# CH32L103K8U6-R0.net
KiCad netlist of a schematic drawn in Altium Designer
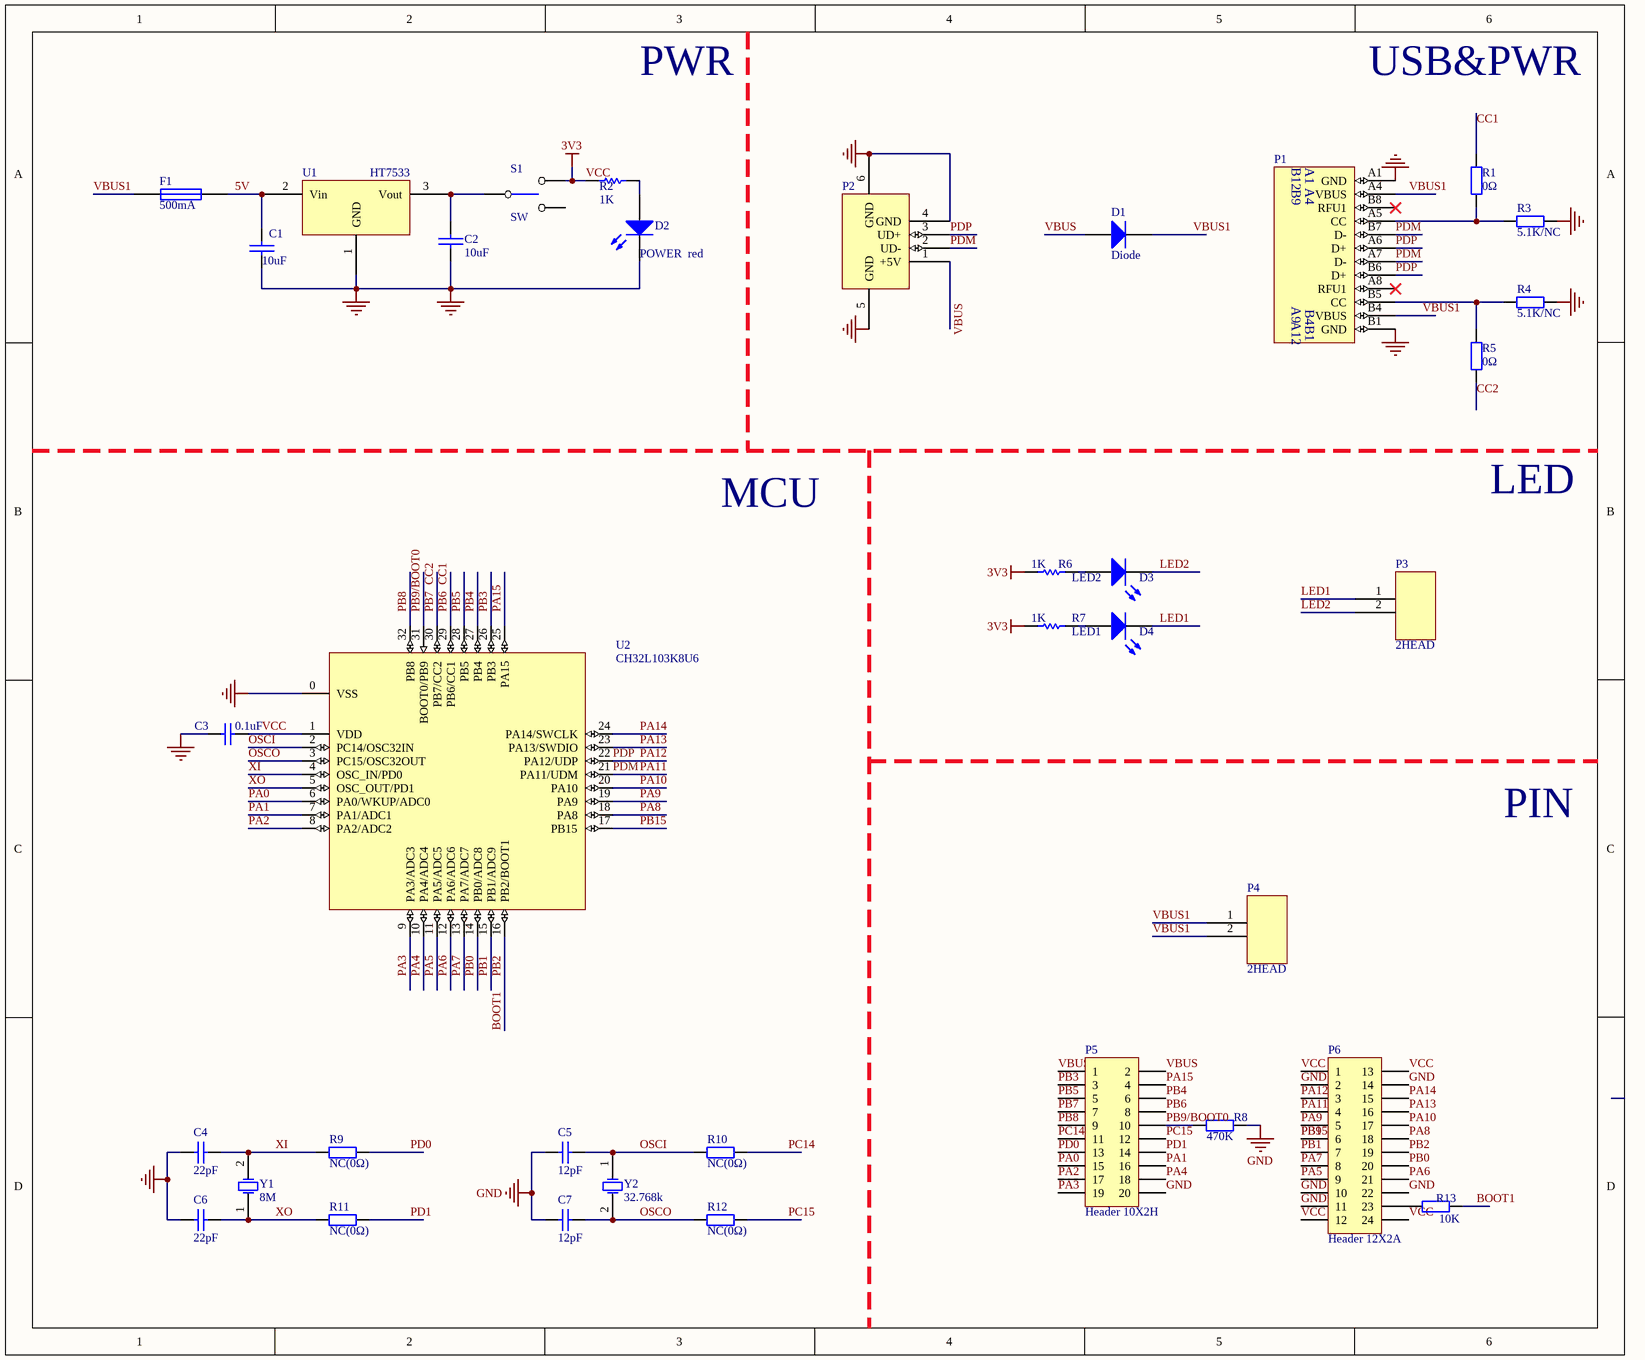
[diagram p0: CH32L103K8U6-R0.SchDoc]

(export (version "E")
  (design (tool "Eeschema 10.0.6"))
  (components
    (comp (ref "C1")
      (value "10uF")
      (footprint "0603_C")
      (description "Capacitor")
      (libsource (lib "*") (part "CAP"))
    )
    (comp (ref "C2")
      (value "10uF")
      (footprint "0603_C")
      (description "Capacitor")
      (libsource (lib "*") (part "CAP"))
    )
    (comp (ref "C3")
      (value "0.1uF")
      (footprint "0603_C")
      (description "Capacitor")
      (fields (field (name "PUBLISHER") "Altium Limited"))
      (libsource (lib "*") (part "Cap"))
    )
    (comp (ref "C4")
      (value "22pF")
      (footprint "0603_C")
      (description "Capacitor")
      (fields (field (name "PUBLISHER") "Altium Limited"))
      (libsource (lib "*") (part "Cap"))
    )
    (comp (ref "C5")
      (value "12pF")
      (footprint "0603")
      (description "Capacitor")
      (fields (field (name "PUBLISHER") "Altium Limited"))
      (libsource (lib "Miscellaneous Devices") (part "Cap"))
    )
    (comp (ref "C6")
      (value "22pF")
      (footprint "0603_C")
      (description "Capacitor")
      (fields (field (name "PUBLISHER") "Altium Limited"))
      (libsource (lib "*") (part "Cap"))
    )
    (comp (ref "C7")
      (value "12pF")
      (footprint "0603")
      (description "Capacitor")
      (fields (field (name "PUBLISHER") "Altium Limited"))
      (libsource (lib "Miscellaneous Devices") (part "Cap"))
    )
    (comp (ref "D1")
      (value "Diode")
      (footprint "SOD-123")
      (description "Default Diode")
      (fields (field (name "PUBLISHER") "Altium Limited"))
      (libsource (lib "Miscellaneous Devices") (part "Diode"))
    )
    (comp (ref "D2")
      (value "POWER  red")
      (footprint "0603+")
      (description "Typical INFRARED GaAs LED")
      (fields (field (name "PUBLISHER") "Altium Limited"))
      (libsource (lib "*") (part "LED0"))
    )
    (comp (ref "D3")
      (value "LED2")
      (footprint "0603+")
      (description "Typical INFRARED GaAs LED")
      (fields (field (name "PUBLISHER") "Altium Limited"))
      (libsource (lib "*") (part "LED0"))
    )
    (comp (ref "D4")
      (value "LED1")
      (footprint "0603+")
      (description "Typical INFRARED GaAs LED")
      (fields (field (name "PUBLISHER") "Altium Limited"))
      (libsource (lib "*") (part "LED0"))
    )
    (comp (ref "F1")
      (value "500mA")
      (footprint "0603")
      (description "Fuse")
      (libsource (lib "*") (part "FUSE1"))
    )
    (comp (ref "P1")
      (value "TYPE-C")
      (footprint "TYPE-C-Receptacle-2.0")
      (libsource (lib "*") (part "TYPE-C1"))
    )
    (comp (ref "P2")
      (value "USB_A")
      (footprint "USBAF")
      (description "USB Port")
      (libsource (lib "*") (part "USB"))
    )
    (comp (ref "P3") (value "2HEAD") (footprint "SIP2-2.54mm") (libsource (lib "*") (part "2HEAD")))
    (comp (ref "P4") (value "2HEAD") (footprint "SIP2-2.54mm") (libsource (lib "*") (part "2HEAD")))
    (comp (ref "P5")
      (value "Header 10X2H")
      (footprint "HDR2X10H")
      (description "Header, 10-Pin, Dual row, Right Angle")
      (fields (field (name "PUBLISHER") "Altium Limited"))
      (libsource (lib "Miscellaneous Connectors") (part "Header 10X2H"))
    )
    (comp (ref "P6")
      (value "Header 12X2A")
      (footprint "HDR2X12_CEN")
      (description "Header, 12-Pin, Dual row")
      (fields (field (name "PUBLISHER") "Altium Limited"))
      (libsource (lib "Miscellaneous Connectors") (part "Header 12X2A"))
    )
    (comp (ref "R1")
      (value "0Ω")
      (footprint "0603")
      (description "Resistor")
      (libsource (lib "Miscellaneous Devices") (part "Res2"))
    )
    (comp (ref "R2")
      (value "1K")
      (footprint "0603")
      (description "Semiconductor Resistor")
      (libsource (lib "*") (part "Res Semi"))
    )
    (comp (ref "R3")
      (value "5.1K/NC")
      (footprint "0603")
      (description "Resistor")
      (libsource (lib "") (part "Res2_2"))
    )
    (comp (ref "R4")
      (value "5.1K/NC")
      (footprint "0603")
      (description "Resistor")
      (libsource (lib "") (part "Res2_2"))
    )
    (comp (ref "R5")
      (value "0Ω")
      (footprint "0603")
      (description "Resistor")
      (libsource (lib "Miscellaneous Devices") (part "Res2"))
    )
    (comp (ref "R6")
      (value "1K")
      (footprint "0603")
      (description "Semiconductor Resistor")
      (libsource (lib "*") (part "Res Semi"))
    )
    (comp (ref "R7")
      (value "1K")
      (footprint "0603")
      (description "Semiconductor Resistor")
      (libsource (lib "*") (part "Res Semi"))
    )
    (comp (ref "R8")
      (value "470K")
      (footprint "0603")
      (description "Resistor")
      (libsource (lib "") (part "Res2_2"))
    )
    (comp (ref "R9")
      (value "NC(0Ω)")
      (footprint "0603")
      (description "Resistor")
      (libsource (lib "") (part "Res2_1"))
    )
    (comp (ref "R10")
      (value "NC(0Ω)")
      (footprint "0603")
      (description "Resistor")
      (libsource (lib "") (part "Res2_1"))
    )
    (comp (ref "R11")
      (value "NC(0Ω)")
      (footprint "0603")
      (description "Resistor")
      (libsource (lib "") (part "Res2_1"))
    )
    (comp (ref "R12")
      (value "NC(0Ω)")
      (footprint "0603")
      (description "Resistor")
      (libsource (lib "") (part "Res2_1"))
    )
    (comp (ref "R13")
      (value "10K")
      (footprint "0603")
      (description "Resistor")
      (fields (field (name "PUBLISHER") "Altium Limited"))
      (libsource (lib "*") (part "Res2"))
    )
    (comp (ref "S1") (value "SW") (footprint "SW1") (libsource (lib "*") (part "SW")))
    (comp (ref "U1")
      (value "HT7533")
      (footprint "SOT-89")
      (libsource (lib "wch_sch_others") (part "1117-3.3V"))
    )
    (comp (ref "U2")
      (value "CH32L103K8U6")
      (footprint "QFN32_4X4")
      (description "RISC-V LMD-MCU, 96MHz, USB, Type-C/PD-5K1, CAN, OPA, lower power")
      (libsource (lib "CHXXX") (part "CH32L103K8U6"))
    )
    (comp (ref "Y1")
      (value "8M")
      (footprint "XT_AT49")
      (description "Crystal Oscillator")
      (fields (field (name "PUBLISHER") "Altium Limited"))
      (libsource (lib "*") (part "XTAL"))
    )
    (comp (ref "Y2")
      (value "32.768k")
      (footprint "FC-135")
      (description "Crystal Oscillator")
      (fields (field (name "PUBLISHER") "Altium Limited"))
      (libsource (lib "Miscellaneous Devices") (part "XTAL"))
    )
  )
  (nets
    (net (code "1") (name "/5V") (class "Default")
      (node (ref "C1") (pin "1") (pinfunction "1_1") (pintype "passive"))
      (node (ref "F1") (pin "2") (pinfunction "2_2") (pintype "passive"))
      (node (ref "U1") (pin "2") (pinfunction "Vin_2") (pintype "passive"))
    )
    (net (code "3") (name "/BOOT1") (class "Default")
      (node (ref "P6") (pin "19") (pinfunction "19_19") (pintype "passive"))
      (node (ref "R13") (pin "2") (pinfunction "2_2") (pintype "passive"))
      (node (ref "U2") (pin "16") (pinfunction "PB2/BOOT1_16") (pintype "bidirectional"))
    )
    (net (code "4") (name "/CC1") (class "Default")
      (node (ref "P5") (pin "8") (pinfunction "8_8") (pintype "passive"))
      (node (ref "R1") (pin "2") (pinfunction "2_2") (pintype "passive"))
      (node (ref "U2") (pin "29") (pinfunction "PB6/CC1_29") (pintype "bidirectional"))
    )
    (net (code "5") (name "/CC2") (class "Default")
      (node (ref "P5") (pin "7") (pinfunction "7_7") (pintype "passive"))
      (node (ref "R5") (pin "1") (pinfunction "1_1") (pintype "passive"))
      (node (ref "U2") (pin "30") (pinfunction "PB7/CC2_30") (pintype "bidirectional"))
    )
    (net (code "6") (name "/LED1") (class "Default")
      (node (ref "D4") (pin "2") (pinfunction "K_2") (pintype "passive"))
      (node (ref "P3") (pin "1") (pintype "passive"))
    )
    (net (code "7") (name "/LED2") (class "Default")
      (node (ref "D3") (pin "2") (pinfunction "K_2") (pintype "passive"))
      (node (ref "P3") (pin "2") (pintype "passive"))
    )
    (net (code "8") (name "/OSCI") (class "Default")
      (node (ref "C5") (pin "1") (pinfunction "1_1") (pintype "passive"))
      (node (ref "R10") (pin "2") (pinfunction "2_2") (pintype "passive"))
      (node (ref "U2") (pin "2") (pinfunction "PC14/OSC32IN_2") (pintype "bidirectional"))
      (node (ref "Y2") (pin "1") (pinfunction "OSC1_1") (pintype "passive"))
    )
    (net (code "9") (name "/OSCO") (class "Default")
      (node (ref "C7") (pin "1") (pinfunction "1_1") (pintype "passive"))
      (node (ref "R12") (pin "2") (pinfunction "2_2") (pintype "passive"))
      (node (ref "U2") (pin "3") (pinfunction "PC15/OSC32OUT_3") (pintype "bidirectional"))
      (node (ref "Y2") (pin "2") (pinfunction "OSC2_2") (pintype "passive"))
    )
    (net (code "10") (name "/PA0") (class "Default")
      (node (ref "P5") (pin "15") (pinfunction "15_15") (pintype "passive"))
      (node (ref "U2") (pin "6") (pinfunction "PA0/WKUP/ADC0_6") (pintype "bidirectional"))
    )
    (net (code "11") (name "/PA1") (class "Default")
      (node (ref "P5") (pin "16") (pinfunction "16_16") (pintype "passive"))
      (node (ref "U2") (pin "7") (pinfunction "PA1/ADC1_7") (pintype "bidirectional"))
    )
    (net (code "12") (name "/PA2") (class "Default")
      (node (ref "P5") (pin "17") (pinfunction "17_17") (pintype "passive"))
      (node (ref "U2") (pin "8") (pinfunction "PA2/ADC2_8") (pintype "bidirectional"))
    )
    (net (code "13") (name "/PA3") (class "Default")
      (node (ref "P5") (pin "19") (pinfunction "19_19") (pintype "passive"))
      (node (ref "U2") (pin "9") (pinfunction "PA3/ADC3_9") (pintype "bidirectional"))
    )
    (net (code "14") (name "/PA4") (class "Default")
      (node (ref "P5") (pin "18") (pinfunction "18_18") (pintype "passive"))
      (node (ref "U2") (pin "10") (pinfunction "PA4/ADC4_10") (pintype "bidirectional"))
    )
    (net (code "15") (name "/PA5") (class "Default")
      (node (ref "P6") (pin "9") (pinfunction "9_9") (pintype "passive"))
      (node (ref "U2") (pin "11") (pinfunction "PA5/ADC5_11") (pintype "bidirectional"))
    )
    (net (code "16") (name "/PA6") (class "Default")
      (node (ref "P6") (pin "21") (pinfunction "21_21") (pintype "passive"))
      (node (ref "U2") (pin "12") (pinfunction "PA6/ADC6_12") (pintype "bidirectional"))
    )
    (net (code "17") (name "/PA7") (class "Default")
      (node (ref "P6") (pin "8") (pinfunction "8_8") (pintype "passive"))
      (node (ref "U2") (pin "13") (pinfunction "PA7/ADC7_13") (pintype "bidirectional"))
    )
    (net (code "18") (name "/PA8") (class "Default")
      (node (ref "P6") (pin "18") (pinfunction "18_18") (pintype "passive"))
      (node (ref "U2") (pin "18") (pinfunction "PA8_18") (pintype "bidirectional"))
    )
    (net (code "19") (name "/PA9") (class "Default")
      (node (ref "P6") (pin "5") (pinfunction "5_5") (pintype "passive"))
      (node (ref "U2") (pin "19") (pinfunction "PA9_19") (pintype "bidirectional"))
    )
    (net (code "20") (name "/PA10") (class "Default")
      (node (ref "P6") (pin "17") (pinfunction "17_17") (pintype "passive"))
      (node (ref "U2") (pin "20") (pinfunction "PA10_20") (pintype "bidirectional"))
    )
    (net (code "21") (name "/PA11") (class "Default")
      (node (ref "P1") (pin "A7") (pinfunction "D-_A7") (pintype "bidirectional"))
      (node (ref "P1") (pin "B7") (pinfunction "D-_B7") (pintype "bidirectional"))
      (node (ref "P2") (pin "2") (pinfunction "UD-_2") (pintype "bidirectional"))
      (node (ref "P6") (pin "4") (pinfunction "4_4") (pintype "passive"))
      (node (ref "U2") (pin "21") (pinfunction "PA11/UDM_21") (pintype "bidirectional"))
    )
    (net (code "22") (name "/PA12") (class "Default")
      (node (ref "P1") (pin "A6") (pinfunction "D+_A6") (pintype "bidirectional"))
      (node (ref "P1") (pin "B6") (pinfunction "D+_B6") (pintype "bidirectional"))
      (node (ref "P2") (pin "3") (pinfunction "UD+_3") (pintype "bidirectional"))
      (node (ref "P6") (pin "3") (pinfunction "3_3") (pintype "passive"))
      (node (ref "U2") (pin "22") (pinfunction "PA12/UDP_22") (pintype "bidirectional"))
    )
    (net (code "23") (name "/PA13") (class "Default")
      (node (ref "P6") (pin "16") (pinfunction "16_16") (pintype "passive"))
      (node (ref "U2") (pin "23") (pinfunction "PA13/SWDIO_23") (pintype "bidirectional"))
    )
    (net (code "24") (name "/PA14") (class "Default")
      (node (ref "P6") (pin "15") (pinfunction "15_15") (pintype "passive"))
      (node (ref "U2") (pin "24") (pinfunction "PA14/SWCLK_24") (pintype "bidirectional"))
    )
    (net (code "25") (name "/PA15") (class "Default")
      (node (ref "P5") (pin "4") (pinfunction "4_4") (pintype "passive"))
      (node (ref "U2") (pin "25") (pinfunction "PA15_25") (pintype "bidirectional"))
    )
    (net (code "26") (name "/PB0") (class "Default")
      (node (ref "P6") (pin "20") (pinfunction "20_20") (pintype "passive"))
      (node (ref "U2") (pin "14") (pinfunction "PB0/ADC8_14") (pintype "bidirectional"))
    )
    (net (code "27") (name "/PB1") (class "Default")
      (node (ref "P6") (pin "7") (pinfunction "7_7") (pintype "passive"))
      (node (ref "U2") (pin "15") (pinfunction "PB1/ADC9_15") (pintype "bidirectional"))
    )
    (net (code "28") (name "/PB3") (class "Default")
      (node (ref "P5") (pin "3") (pinfunction "3_3") (pintype "passive"))
      (node (ref "U2") (pin "26") (pinfunction "PB3_26") (pintype "bidirectional"))
    )
    (net (code "29") (name "/PB4") (class "Default")
      (node (ref "P5") (pin "6") (pinfunction "6_6") (pintype "passive"))
      (node (ref "U2") (pin "27") (pinfunction "PB4_27") (pintype "bidirectional"))
    )
    (net (code "30") (name "/PB5") (class "Default")
      (node (ref "P5") (pin "5") (pinfunction "5_5") (pintype "passive"))
      (node (ref "U2") (pin "28") (pinfunction "PB5_28") (pintype "bidirectional"))
    )
    (net (code "31") (name "/PB8") (class "Default")
      (node (ref "P5") (pin "9") (pinfunction "9_9") (pintype "passive"))
      (node (ref "U2") (pin "32") (pinfunction "PB8_32") (pintype "bidirectional"))
    )
    (net (code "32") (name "/PB9{slash}BOOT0") (class "Default")
      (node (ref "P5") (pin "10") (pinfunction "10_10") (pintype "passive"))
      (node (ref "R8") (pin "1") (pinfunction "1_1") (pintype "passive"))
      (node (ref "U2") (pin "31") (pinfunction "BOOT0/PB9_31") (pintype "input"))
    )
    (net (code "33") (name "/PB15") (class "Default")
      (node (ref "P6") (pin "6") (pinfunction "6_6") (pintype "passive"))
      (node (ref "U2") (pin "17") (pinfunction "PB15_17") (pintype "bidirectional"))
    )
    (net (code "34") (name "/PC14") (class "Default")
      (node (ref "P5") (pin "11") (pinfunction "11_11") (pintype "passive"))
      (node (ref "R10") (pin "1") (pinfunction "1_1") (pintype "passive"))
    )
    (net (code "35") (name "/PC15") (class "Default")
      (node (ref "P5") (pin "12") (pinfunction "12_12") (pintype "passive"))
      (node (ref "R12") (pin "1") (pinfunction "1_1") (pintype "passive"))
    )
    (net (code "36") (name "/PD0") (class "Default")
      (node (ref "P5") (pin "13") (pinfunction "13_13") (pintype "passive"))
      (node (ref "R9") (pin "1") (pinfunction "1_1") (pintype "passive"))
    )
    (net (code "37") (name "/PD1") (class "Default")
      (node (ref "P5") (pin "14") (pinfunction "14_14") (pintype "passive"))
      (node (ref "R11") (pin "1") (pinfunction "1_1") (pintype "passive"))
    )
    (net (code "38") (name "/VBUS") (class "Default")
      (node (ref "D1") (pin "1") (pinfunction "A_1") (pintype "passive"))
      (node (ref "P2") (pin "1") (pinfunction "+5V_1") (pintype "power_in"))
      (node (ref "P5") (pin "1") (pinfunction "1_1") (pintype "passive"))
      (node (ref "P5") (pin "2") (pinfunction "2_2") (pintype "passive"))
    )
    (net (code "39") (name "/VBUS1") (class "Default")
      (node (ref "D1") (pin "2") (pinfunction "K_2") (pintype "passive"))
      (node (ref "F1") (pin "1") (pinfunction "1_1") (pintype "passive"))
      (node (ref "P1") (pin "A4") (pinfunction "VBUS_A4") (pintype "bidirectional"))
      (node (ref "P1") (pin "B4") (pinfunction "VBUS_B4") (pintype "bidirectional"))
      (node (ref "P4") (pin "1") (pintype "passive"))
      (node (ref "P4") (pin "2") (pintype "passive"))
    )
    (net (code "40") (name "/XI") (class "Default")
      (node (ref "C4") (pin "2") (pinfunction "2_2") (pintype "passive"))
      (node (ref "R9") (pin "2") (pinfunction "2_2") (pintype "passive"))
      (node (ref "U2") (pin "4") (pinfunction "OSC_IN/PD0_4") (pintype "bidirectional"))
      (node (ref "Y1") (pin "2") (pinfunction "OSC2_2") (pintype "passive"))
    )
    (net (code "41") (name "/XO") (class "Default")
      (node (ref "C6") (pin "2") (pinfunction "2_2") (pintype "passive"))
      (node (ref "R11") (pin "2") (pinfunction "2_2") (pintype "passive"))
      (node (ref "U2") (pin "5") (pinfunction "OSC_OUT/PD1_5") (pintype "bidirectional"))
      (node (ref "Y1") (pin "1") (pinfunction "OSC1_1") (pintype "passive"))
    )
    (net (code "42") (name "3V3") (class "Default")
      (node (ref "C3") (pin "1") (pinfunction "1_1") (pintype "passive"))
      (node (ref "P6") (pin "1") (pinfunction "1_1") (pintype "passive"))
      (node (ref "P6") (pin "12") (pinfunction "12_12") (pintype "passive"))
      (node (ref "P6") (pin "13") (pinfunction "13_13") (pintype "passive"))
      (node (ref "P6") (pin "24") (pinfunction "24_24") (pintype "passive"))
      (node (ref "R2") (pin "2") (pinfunction "2_2") (pintype "passive"))
      (node (ref "R6") (pin "1") (pinfunction "1_1") (pintype "passive"))
      (node (ref "R7") (pin "1") (pinfunction "1_1") (pintype "passive"))
      (node (ref "S1") (pin "3") (pinfunction "3_3") (pintype "passive"))
      (node (ref "U2") (pin "1") (pinfunction "VDD_1") (pintype "power_in"))
    )
    (net (code "43") (name "GND") (class "Default")
      (node (ref "C1") (pin "2") (pinfunction "2_2") (pintype "passive"))
      (node (ref "C2") (pin "2") (pinfunction "2_2") (pintype "passive"))
      (node (ref "C3") (pin "2") (pinfunction "2_2") (pintype "passive"))
      (node (ref "C4") (pin "1") (pinfunction "1_1") (pintype "passive"))
      (node (ref "C5") (pin "2") (pinfunction "2_2") (pintype "passive"))
      (node (ref "C6") (pin "1") (pinfunction "1_1") (pintype "passive"))
      (node (ref "C7") (pin "2") (pinfunction "2_2") (pintype "passive"))
      (node (ref "D2") (pin "2") (pinfunction "K_2") (pintype "passive"))
      (node (ref "P1") (pin "A1") (pinfunction "GND_A1") (pintype "bidirectional"))
      (node (ref "P1") (pin "B1") (pinfunction "GND_B1") (pintype "bidirectional"))
      (node (ref "P2") (pin "4") (pinfunction "GND_4") (pintype "power_in"))
      (node (ref "P2") (pin "5") (pinfunction "GND_5") (pintype "power_in"))
      (node (ref "P2") (pin "6") (pinfunction "GND_6") (pintype "power_in"))
      (node (ref "P5") (pin "20") (pinfunction "20_20") (pintype "passive"))
      (node (ref "P6") (pin "10") (pinfunction "10_10") (pintype "passive"))
      (node (ref "P6") (pin "11") (pinfunction "11_11") (pintype "passive"))
      (node (ref "P6") (pin "14") (pinfunction "14_14") (pintype "passive"))
      (node (ref "P6") (pin "2") (pinfunction "2_2") (pintype "passive"))
      (node (ref "P6") (pin "22") (pinfunction "22_22") (pintype "passive"))
      (node (ref "R3") (pin "2") (pinfunction "2_2") (pintype "passive"))
      (node (ref "R4") (pin "2") (pinfunction "2_2") (pintype "passive"))
      (node (ref "R8") (pin "2") (pinfunction "2_2") (pintype "passive"))
      (node (ref "U1") (pin "1") (pinfunction "GND_1") (pintype "passive"))
      (node (ref "U2") (pin "0") (pinfunction "VSS_0") (pintype "power_in"))
    )
    (net (code "44") (name "Net-(D2-A)") (class "Default")
      (node (ref "D2") (pin "1") (pinfunction "A_1") (pintype "passive"))
      (node (ref "R2") (pin "1") (pinfunction "1_1") (pintype "passive"))
    )
    (net (code "45") (name "Net-(D3-A)") (class "Default")
      (node (ref "D3") (pin "1") (pinfunction "A_1") (pintype "passive"))
      (node (ref "R6") (pin "2") (pinfunction "2_2") (pintype "passive"))
    )
    (net (code "46") (name "Net-(D4-A)") (class "Default")
      (node (ref "D4") (pin "1") (pinfunction "A_1") (pintype "passive"))
      (node (ref "R7") (pin "2") (pinfunction "2_2") (pintype "passive"))
    )
    (net (code "47") (name "Net-(P1-CC-PadA5)") (class "Default")
      (node (ref "P1") (pin "A5") (pinfunction "CC_A5") (pintype "bidirectional"))
      (node (ref "R1") (pin "1") (pinfunction "1_1") (pintype "passive"))
      (node (ref "R3") (pin "1") (pinfunction "1_1") (pintype "passive"))
    )
    (net (code "48") (name "Net-(P1-CC-PadB5)") (class "Default")
      (node (ref "P1") (pin "B5") (pinfunction "CC_B5") (pintype "bidirectional"))
      (node (ref "R4") (pin "1") (pinfunction "1_1") (pintype "passive"))
      (node (ref "R5") (pin "2") (pinfunction "2_2") (pintype "passive"))
    )
    (net (code "49") (name "Net-(P6-Pad23)") (class "Default")
      (node (ref "P6") (pin "23") (pinfunction "23_23") (pintype "passive"))
      (node (ref "R13") (pin "1") (pinfunction "1_1") (pintype "passive"))
    )
    (net (code "50") (name "Net-(U1-Vout)") (class "Default")
      (node (ref "C2") (pin "1") (pinfunction "1_1") (pintype "passive"))
      (node (ref "S1") (pin "1") (pinfunction "1_1") (pintype "passive"))
      (node (ref "U1") (pin "3") (pinfunction "Vout_3") (pintype "passive"))
    )
    (net (code "51") (name "unconnected-(P1-RFU1-PadA8)") (class "Default")
      (node (ref "P1") (pin "A8") (pinfunction "RFU1_A8") (pintype "bidirectional+no_connect"))
    )
    (net (code "52") (name "unconnected-(P1-RFU1-PadB8)") (class "Default")
      (node (ref "P1") (pin "B8") (pinfunction "RFU1_B8") (pintype "bidirectional+no_connect"))
    )
    (net (code "53") (name "unconnected-(S1-Pad2)") (class "Default")
      (node (ref "S1") (pin "2") (pinfunction "2_2") (pintype "passive"))
    )
  )
)
